# MCX_BNC_Adapter.net
KiCad netlist of a schematic drawn in Altium Designer
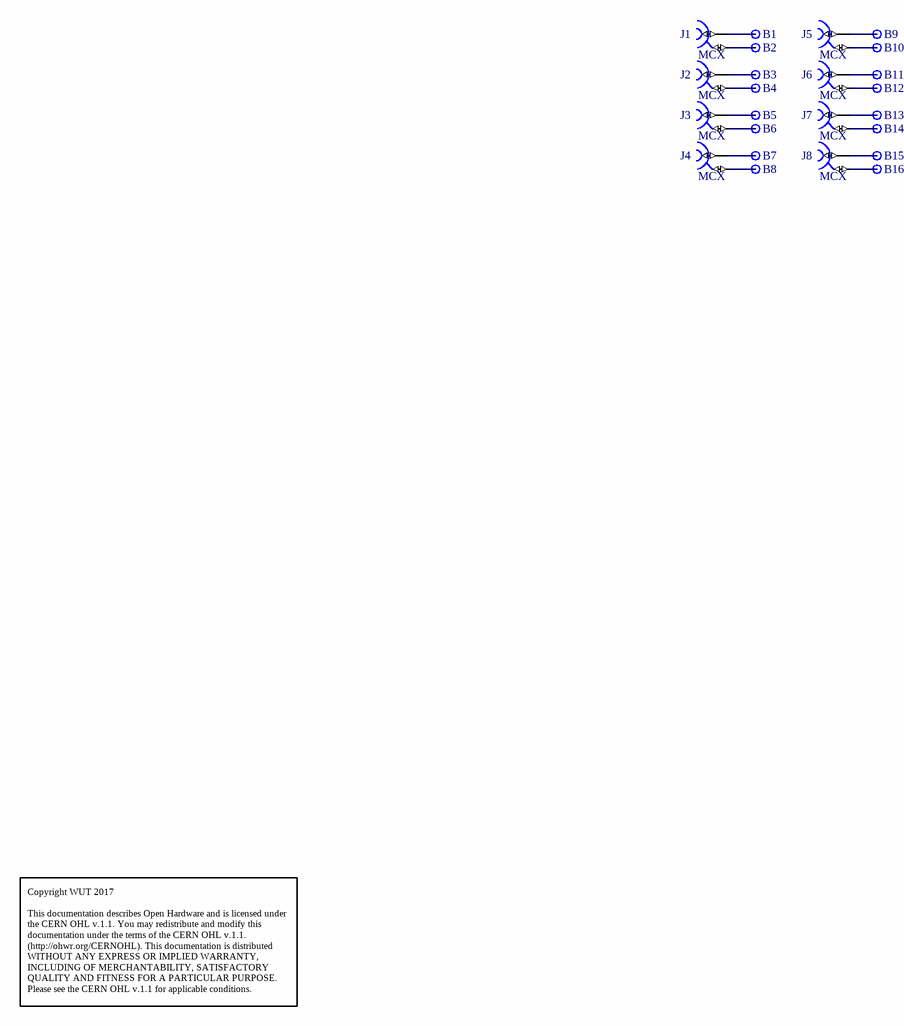
[diagram p0: MCX_BNC_Adapter.SchDoc]

(export (version "E")
  (design (tool "Eeschema 10.0.6"))
  (components
    (comp (ref "B1")
      (value "Plated Hole")
      (footprint "c160h90")
      (description "Single Terminal Socket")
      (fields (field (name "PART NUMBER") "PLATED_HOLE0.9_PAD1.6") (field (name "AUTHOR") "CERN DEM JLC"))
      (libsource (lib "Eletro-mechanical") (part "Single Terminal Socket"))
    )
    (comp (ref "B2")
      (value "Plated Hole")
      (footprint "c160h90")
      (description "Single Terminal Socket")
      (fields (field (name "PART NUMBER") "PLATED_HOLE0.9_PAD1.6") (field (name "AUTHOR") "CERN DEM JLC"))
      (libsource (lib "Eletro-mechanical") (part "Single Terminal Socket"))
    )
    (comp (ref "B3")
      (value "Plated Hole")
      (footprint "c160h90")
      (description "Single Terminal Socket")
      (fields (field (name "PART NUMBER") "PLATED_HOLE0.9_PAD1.6") (field (name "AUTHOR") "CERN DEM JLC"))
      (libsource (lib "Eletro-mechanical") (part "Single Terminal Socket"))
    )
    (comp (ref "B4")
      (value "Plated Hole")
      (footprint "c160h90")
      (description "Single Terminal Socket")
      (fields (field (name "PART NUMBER") "PLATED_HOLE0.9_PAD1.6") (field (name "AUTHOR") "CERN DEM JLC"))
      (libsource (lib "Eletro-mechanical") (part "Single Terminal Socket"))
    )
    (comp (ref "B5")
      (value "Plated Hole")
      (footprint "c160h90")
      (description "Single Terminal Socket")
      (fields (field (name "PART NUMBER") "PLATED_HOLE0.9_PAD1.6") (field (name "AUTHOR") "CERN DEM JLC"))
      (libsource (lib "Eletro-mechanical") (part "Single Terminal Socket"))
    )
    (comp (ref "B6")
      (value "Plated Hole")
      (footprint "c160h90")
      (description "Single Terminal Socket")
      (fields (field (name "PART NUMBER") "PLATED_HOLE0.9_PAD1.6") (field (name "AUTHOR") "CERN DEM JLC"))
      (libsource (lib "Eletro-mechanical") (part "Single Terminal Socket"))
    )
    (comp (ref "B7")
      (value "Plated Hole")
      (footprint "c160h90")
      (description "Single Terminal Socket")
      (fields (field (name "PART NUMBER") "PLATED_HOLE0.9_PAD1.6") (field (name "AUTHOR") "CERN DEM JLC"))
      (libsource (lib "Eletro-mechanical") (part "Single Terminal Socket"))
    )
    (comp (ref "B8")
      (value "Plated Hole")
      (footprint "c160h90")
      (description "Single Terminal Socket")
      (fields (field (name "PART NUMBER") "PLATED_HOLE0.9_PAD1.6") (field (name "AUTHOR") "CERN DEM JLC"))
      (libsource (lib "Eletro-mechanical") (part "Single Terminal Socket"))
    )
    (comp (ref "B9")
      (value "Plated Hole")
      (footprint "c160h90")
      (description "Single Terminal Socket")
      (fields (field (name "PART NUMBER") "PLATED_HOLE0.9_PAD1.6") (field (name "AUTHOR") "CERN DEM JLC"))
      (libsource (lib "Eletro-mechanical") (part "Single Terminal Socket"))
    )
    (comp (ref "B10")
      (value "Plated Hole")
      (footprint "c160h90")
      (description "Single Terminal Socket")
      (fields (field (name "PART NUMBER") "PLATED_HOLE0.9_PAD1.6") (field (name "AUTHOR") "CERN DEM JLC"))
      (libsource (lib "Eletro-mechanical") (part "Single Terminal Socket"))
    )
    (comp (ref "B11")
      (value "Plated Hole")
      (footprint "c160h90")
      (description "Single Terminal Socket")
      (fields (field (name "PART NUMBER") "PLATED_HOLE0.9_PAD1.6") (field (name "AUTHOR") "CERN DEM JLC"))
      (libsource (lib "Eletro-mechanical") (part "Single Terminal Socket"))
    )
    (comp (ref "B12")
      (value "Plated Hole")
      (footprint "c160h90")
      (description "Single Terminal Socket")
      (fields (field (name "PART NUMBER") "PLATED_HOLE0.9_PAD1.6") (field (name "AUTHOR") "CERN DEM JLC"))
      (libsource (lib "Eletro-mechanical") (part "Single Terminal Socket"))
    )
    (comp (ref "B13")
      (value "Plated Hole")
      (footprint "c160h90")
      (description "Single Terminal Socket")
      (fields (field (name "PART NUMBER") "PLATED_HOLE0.9_PAD1.6") (field (name "AUTHOR") "CERN DEM JLC"))
      (libsource (lib "Eletro-mechanical") (part "Single Terminal Socket"))
    )
    (comp (ref "B14")
      (value "Plated Hole")
      (footprint "c160h90")
      (description "Single Terminal Socket")
      (fields (field (name "PART NUMBER") "PLATED_HOLE0.9_PAD1.6") (field (name "AUTHOR") "CERN DEM JLC"))
      (libsource (lib "Eletro-mechanical") (part "Single Terminal Socket"))
    )
    (comp (ref "B15")
      (value "Plated Hole")
      (footprint "c160h90")
      (description "Single Terminal Socket")
      (fields (field (name "PART NUMBER") "PLATED_HOLE0.9_PAD1.6") (field (name "AUTHOR") "CERN DEM JLC"))
      (libsource (lib "Eletro-mechanical") (part "Single Terminal Socket"))
    )
    (comp (ref "B16")
      (value "Plated Hole")
      (footprint "c160h90")
      (description "Single Terminal Socket")
      (fields (field (name "PART NUMBER") "PLATED_HOLE0.9_PAD1.6") (field (name "AUTHOR") "CERN DEM JLC"))
      (libsource (lib "Eletro-mechanical") (part "Single Terminal Socket"))
    )
    (comp (ref "J1")
      (value "MCX")
      (footprint "AMPHENOL_919-383J-51A")
      (fields
        (field (name "PART NUMBER") "AMPHENOL_919-383J-51A")
        (field (name "MANUFACTURER") "AMPHENOL")
        (field (name "MANUFACTURER PART NUMBER") "919-383J-51A")
        (field (name "AUTHOR") "CERN DEM BC")
      )
      (libsource (lib "Connectors") (part "Coax_1Female_1Shield"))
    )
    (comp (ref "J2")
      (value "MCX")
      (footprint "AMPHENOL_919-383J-51A")
      (fields
        (field (name "PART NUMBER") "AMPHENOL_919-383J-51A")
        (field (name "MANUFACTURER") "AMPHENOL")
        (field (name "MANUFACTURER PART NUMBER") "919-383J-51A")
        (field (name "AUTHOR") "CERN DEM BC")
      )
      (libsource (lib "Connectors") (part "Coax_1Female_1Shield"))
    )
    (comp (ref "J3")
      (value "MCX")
      (footprint "AMPHENOL_919-383J-51A")
      (fields
        (field (name "PART NUMBER") "AMPHENOL_919-383J-51A")
        (field (name "MANUFACTURER") "AMPHENOL")
        (field (name "MANUFACTURER PART NUMBER") "919-383J-51A")
        (field (name "AUTHOR") "CERN DEM BC")
      )
      (libsource (lib "Connectors") (part "Coax_1Female_1Shield"))
    )
    (comp (ref "J4")
      (value "MCX")
      (footprint "AMPHENOL_919-383J-51A")
      (fields
        (field (name "PART NUMBER") "AMPHENOL_919-383J-51A")
        (field (name "MANUFACTURER") "AMPHENOL")
        (field (name "MANUFACTURER PART NUMBER") "919-383J-51A")
        (field (name "AUTHOR") "CERN DEM BC")
      )
      (libsource (lib "Connectors") (part "Coax_1Female_1Shield"))
    )
    (comp (ref "J5")
      (value "MCX")
      (footprint "AMPHENOL_919-383J-51A")
      (fields
        (field (name "PART NUMBER") "AMPHENOL_919-383J-51A")
        (field (name "MANUFACTURER") "AMPHENOL")
        (field (name "MANUFACTURER PART NUMBER") "919-383J-51A")
        (field (name "AUTHOR") "CERN DEM BC")
      )
      (libsource (lib "Connectors") (part "Coax_1Female_1Shield"))
    )
    (comp (ref "J6")
      (value "MCX")
      (footprint "AMPHENOL_919-383J-51A")
      (fields
        (field (name "PART NUMBER") "AMPHENOL_919-383J-51A")
        (field (name "MANUFACTURER") "AMPHENOL")
        (field (name "MANUFACTURER PART NUMBER") "919-383J-51A")
        (field (name "AUTHOR") "CERN DEM BC")
      )
      (libsource (lib "Connectors") (part "Coax_1Female_1Shield"))
    )
    (comp (ref "J7")
      (value "MCX")
      (footprint "AMPHENOL_919-383J-51A")
      (fields
        (field (name "PART NUMBER") "AMPHENOL_919-383J-51A")
        (field (name "MANUFACTURER") "AMPHENOL")
        (field (name "MANUFACTURER PART NUMBER") "919-383J-51A")
        (field (name "AUTHOR") "CERN DEM BC")
      )
      (libsource (lib "Connectors") (part "Coax_1Female_1Shield"))
    )
    (comp (ref "J8")
      (value "MCX")
      (footprint "AMPHENOL_919-383J-51A")
      (fields
        (field (name "PART NUMBER") "AMPHENOL_919-383J-51A")
        (field (name "MANUFACTURER") "AMPHENOL")
        (field (name "MANUFACTURER PART NUMBER") "919-383J-51A")
        (field (name "AUTHOR") "CERN DEM BC")
      )
      (libsource (lib "Connectors") (part "Coax_1Female_1Shield"))
    )
  )
  (nets
    (net (code "1") (name "Net-(B1-Pad1)") (class "Default")
      (node (ref "B1") (pin "1") (pinfunction "1_1") (pintype "bidirectional"))
      (node (ref "J1") (pin "1") (pinfunction "1_1") (pintype "bidirectional"))
    )
    (net (code "2") (name "Net-(B2-Pad1)") (class "Default")
      (node (ref "B2") (pin "1") (pinfunction "1_1") (pintype "bidirectional"))
      (node (ref "J1") (pin "2") (pinfunction "2_2") (pintype "bidirectional"))
    )
    (net (code "3") (name "Net-(B3-Pad1)") (class "Default")
      (node (ref "B3") (pin "1") (pinfunction "1_1") (pintype "bidirectional"))
      (node (ref "J2") (pin "1") (pinfunction "1_1") (pintype "bidirectional"))
    )
    (net (code "4") (name "Net-(B4-Pad1)") (class "Default")
      (node (ref "B4") (pin "1") (pinfunction "1_1") (pintype "bidirectional"))
      (node (ref "J2") (pin "2") (pinfunction "2_2") (pintype "bidirectional"))
    )
    (net (code "5") (name "Net-(B5-Pad1)") (class "Default")
      (node (ref "B5") (pin "1") (pinfunction "1_1") (pintype "bidirectional"))
      (node (ref "J3") (pin "1") (pinfunction "1_1") (pintype "bidirectional"))
    )
    (net (code "6") (name "Net-(B6-Pad1)") (class "Default")
      (node (ref "B6") (pin "1") (pinfunction "1_1") (pintype "bidirectional"))
      (node (ref "J3") (pin "2") (pinfunction "2_2") (pintype "bidirectional"))
    )
    (net (code "7") (name "Net-(B7-Pad1)") (class "Default")
      (node (ref "B7") (pin "1") (pinfunction "1_1") (pintype "bidirectional"))
      (node (ref "J4") (pin "1") (pinfunction "1_1") (pintype "bidirectional"))
    )
    (net (code "8") (name "Net-(B8-Pad1)") (class "Default")
      (node (ref "B8") (pin "1") (pinfunction "1_1") (pintype "bidirectional"))
      (node (ref "J4") (pin "2") (pinfunction "2_2") (pintype "bidirectional"))
    )
    (net (code "9") (name "Net-(B9-Pad1)") (class "Default")
      (node (ref "B9") (pin "1") (pinfunction "1_1") (pintype "bidirectional"))
      (node (ref "J5") (pin "1") (pinfunction "1_1") (pintype "bidirectional"))
    )
    (net (code "10") (name "Net-(B10-Pad1)") (class "Default")
      (node (ref "B10") (pin "1") (pinfunction "1_1") (pintype "bidirectional"))
      (node (ref "J5") (pin "2") (pinfunction "2_2") (pintype "bidirectional"))
    )
    (net (code "11") (name "Net-(B11-Pad1)") (class "Default")
      (node (ref "B11") (pin "1") (pinfunction "1_1") (pintype "bidirectional"))
      (node (ref "J6") (pin "1") (pinfunction "1_1") (pintype "bidirectional"))
    )
    (net (code "12") (name "Net-(B12-Pad1)") (class "Default")
      (node (ref "B12") (pin "1") (pinfunction "1_1") (pintype "bidirectional"))
      (node (ref "J6") (pin "2") (pinfunction "2_2") (pintype "bidirectional"))
    )
    (net (code "13") (name "Net-(B13-Pad1)") (class "Default")
      (node (ref "B13") (pin "1") (pinfunction "1_1") (pintype "bidirectional"))
      (node (ref "J7") (pin "1") (pinfunction "1_1") (pintype "bidirectional"))
    )
    (net (code "14") (name "Net-(B14-Pad1)") (class "Default")
      (node (ref "B14") (pin "1") (pinfunction "1_1") (pintype "bidirectional"))
      (node (ref "J7") (pin "2") (pinfunction "2_2") (pintype "bidirectional"))
    )
    (net (code "15") (name "Net-(B15-Pad1)") (class "Default")
      (node (ref "B15") (pin "1") (pinfunction "1_1") (pintype "bidirectional"))
      (node (ref "J8") (pin "1") (pinfunction "1_1") (pintype "bidirectional"))
    )
    (net (code "16") (name "Net-(B16-Pad1)") (class "Default")
      (node (ref "B16") (pin "1") (pinfunction "1_1") (pintype "bidirectional"))
      (node (ref "J8") (pin "2") (pinfunction "2_2") (pintype "bidirectional"))
    )
  )
)
